# SeptinaryAI_Balldi__elec_power__power_20.net
KiCad netlist of a schematic drawn in Altium Designer
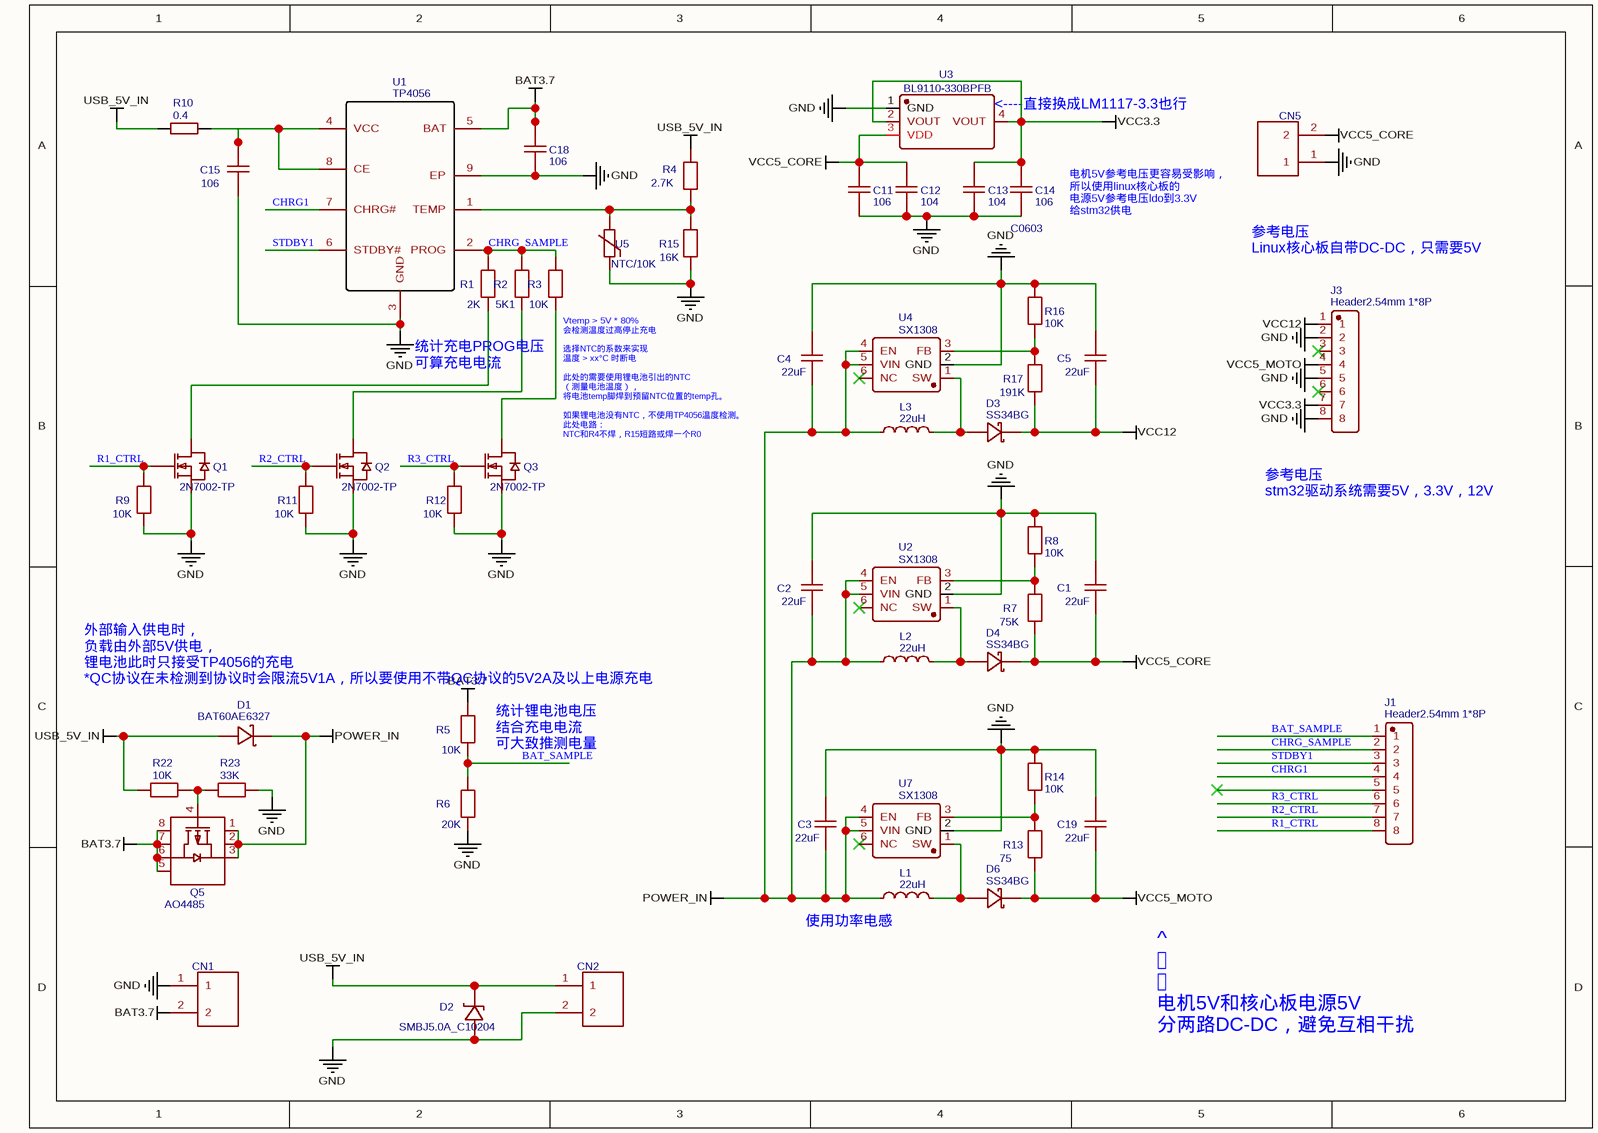
[diagram p0: SeptinaryAI_Balldi__elec_power__power_2023-07-21.schdoc]

(export (version "E")
  (design (tool "Eeschema 10.0.6"))
  (components
    (comp (ref "C1")
      (value "22uF")
      (fields (field (name "CONTRIBUTOR") "LCSC"))
      (libsource (lib "altium-import") (part "root_1_22uF_"))
    )
    (comp (ref "C2")
      (value "22uF")
      (fields (field (name "CONTRIBUTOR") "LCSC"))
      (libsource (lib "altium-import") (part "root_1_22uF_"))
    )
    (comp (ref "C3")
      (value "22uF")
      (fields (field (name "CONTRIBUTOR") "LCSC"))
      (libsource (lib "altium-import") (part "root_1_22uF_"))
    )
    (comp (ref "C4")
      (value "22uF")
      (fields (field (name "CONTRIBUTOR") "LCSC"))
      (libsource (lib "altium-import") (part "root_1_22uF_"))
    )
    (comp (ref "C5")
      (value "22uF")
      (fields (field (name "CONTRIBUTOR") "LCSC"))
      (libsource (lib "altium-import") (part "root_1_22uF_"))
    )
    (comp (ref "C11")
      (value "106")
      (fields
        (field (name "BOM_SUPPLIER PART") "C2762283")
        (field (name "BOM_MANUFACTURER PART") "CL10F104ZO8NNNC")
        (field (name "CONTRIBUTOR") "LCSC")
      )
      (libsource (lib "altium-import") (part "root_1_106_"))
    )
    (comp (ref "C12")
      (value "104")
      (fields
        (field (name "BOM_SUPPLIER PART") "C2762283")
        (field (name "BOM_MANUFACTURER PART") "CL10F104ZO8NNNC")
        (field (name "CONTRIBUTOR") "LCSC")
      )
      (libsource (lib "altium-import") (part "root_1_104_"))
    )
    (comp (ref "C13")
      (value "104")
      (fields
        (field (name "BOM_SUPPLIER PART") "C2762283")
        (field (name "BOM_MANUFACTURER PART") "CL10F104ZO8NNNC")
        (field (name "CONTRIBUTOR") "LCSC")
      )
      (libsource (lib "altium-import") (part "root_1_104_"))
    )
    (comp (ref "C14")
      (value "106")
      (fields
        (field (name "BOM_SUPPLIER PART") "C2762283")
        (field (name "BOM_MANUFACTURER PART") "CL10F104ZO8NNNC")
        (field (name "CONTRIBUTOR") "LCSC")
      )
      (libsource (lib "altium-import") (part "root_1_106_"))
    )
    (comp (ref "C15")
      (value "106")
      (fields (field (name "CONTRIBUTOR") "LCSC"))
      (libsource (lib "altium-import") (part "root_1_106_"))
    )
    (comp (ref "C18")
      (value "106")
      (fields (field (name "CONTRIBUTOR") "LCSC"))
      (libsource (lib "altium-import") (part "root_1_106_"))
    )
    (comp (ref "C19")
      (value "22uF")
      (fields (field (name "CONTRIBUTOR") "LCSC"))
      (libsource (lib "altium-import") (part "root_1_22uF_"))
    )
    (comp (ref "CN1") (value "640454-2") (libsource (lib "altium-import") (part "root_0_640454-2_")))
    (comp (ref "CN2") (value "640454-2") (libsource (lib "altium-import") (part "root_0_640454-2_")))
    (comp (ref "CN5") (value "640454-2") (libsource (lib "altium-import") (part "root_2_640454-2_")))
    (comp (ref "D1")
      (value "BAT60AE6327")
      (fields (field (name "CONTRIBUTOR") "LCSC"))
      (libsource (lib "altium-import") (part "root_0_BAT60AE6327_"))
    )
    (comp (ref "D2")
      (value "SMBJ5.0A_C10204")
      (libsource (lib "altium-import") (part "root_3_SMBJ5.0A_C10204_"))
    )
    (comp (ref "D3")
      (value "SS34BG")
      (fields (field (name "BOM_SUPPLIER PART") "C719397") (field (name "CONTRIBUTOR") "LCSC"))
      (libsource (lib "altium-import") (part "root_2_SS34BG_"))
    )
    (comp (ref "D4")
      (value "SS34BG")
      (fields (field (name "BOM_SUPPLIER PART") "C719397") (field (name "CONTRIBUTOR") "LCSC"))
      (libsource (lib "altium-import") (part "root_2_SS34BG_"))
    )
    (comp (ref "D6")
      (value "SS34BG")
      (fields (field (name "BOM_SUPPLIER PART") "C719397") (field (name "CONTRIBUTOR") "LCSC"))
      (libsource (lib "altium-import") (part "root_2_SS34BG_"))
    )
    (comp (ref "J1")
      (value "Header2.54mm 1*8P")
      (libsource (lib "altium-import") (part "root_0_Header2.54mm 1*8P_"))
    )
    (comp (ref "J3")
      (value "Header2.54mm 1*8P")
      (libsource (lib "altium-import") (part "root_0_Header2.54mm 1*8P_"))
    )
    (comp (ref "L1")
      (value "22uH")
      (fields
        (field (name "BOM_MANUFACTURER PART") "SPM10040T-220M")
        (field (name "BOM_SUPPLIER PART") "C138686")
      )
      (libsource (lib "altium-import") (part "root_0_22uH_"))
    )
    (comp (ref "L2")
      (value "22uH")
      (fields
        (field (name "BOM_MANUFACTURER PART") "SPM10040T-220M")
        (field (name "BOM_SUPPLIER PART") "C138686")
      )
      (libsource (lib "altium-import") (part "root_0_22uH_"))
    )
    (comp (ref "L3")
      (value "22uH")
      (fields
        (field (name "BOM_MANUFACTURER PART") "SPM10040T-220M")
        (field (name "BOM_SUPPLIER PART") "C138686")
      )
      (libsource (lib "altium-import") (part "root_0_22uH_"))
    )
    (comp (ref "Q1")
      (value "2N7002-TP")
      (fields (field (name "CONTRIBUTOR") "LCSC"))
      (libsource (lib "altium-import") (part "root_0_2N7002-TP_"))
    )
    (comp (ref "Q2")
      (value "2N7002-TP")
      (fields (field (name "CONTRIBUTOR") "LCSC"))
      (libsource (lib "altium-import") (part "root_0_2N7002-TP_"))
    )
    (comp (ref "Q3")
      (value "2N7002-TP")
      (fields (field (name "CONTRIBUTOR") "LCSC"))
      (libsource (lib "altium-import") (part "root_0_2N7002-TP_"))
    )
    (comp (ref "Q5")
      (value "AO4485")
      (fields (field (name "BOM_SUPPLIER PART") "C51499"))
      (libsource (lib "altium-import") (part "root_3_AO4485_"))
    )
    (comp (ref "R1")
      (value "2K")
      (fields (field (name "CONTRIBUTOR") "LCSC"))
      (libsource (lib "altium-import") (part "root_3_2K_"))
    )
    (comp (ref "R2")
      (value "5K1")
      (fields (field (name "CONTRIBUTOR") "LCSC"))
      (libsource (lib "altium-import") (part "root_3_5K1_"))
    )
    (comp (ref "R3")
      (value "10K")
      (fields (field (name "CONTRIBUTOR") "LCSC"))
      (libsource (lib "altium-import") (part "root_3_10K_"))
    )
    (comp (ref "R4")
      (value "2.7K")
      (fields (field (name "CONTRIBUTOR") "LCSC"))
      (libsource (lib "altium-import") (part "root_3_2.7K_"))
    )
    (comp (ref "R5")
      (value "10K")
      (fields (field (name "CONTRIBUTOR") "LCSC"))
      (libsource (lib "altium-import") (part "root_3_10K_"))
    )
    (comp (ref "R6")
      (value "20K")
      (fields (field (name "CONTRIBUTOR") "LCSC"))
      (libsource (lib "altium-import") (part "root_3_20K_"))
    )
    (comp (ref "R7")
      (value "75K")
      (fields (field (name "CONTRIBUTOR") "LCSC"))
      (libsource (lib "altium-import") (part "root_3_75K_"))
    )
    (comp (ref "R8")
      (value "10K")
      (fields (field (name "CONTRIBUTOR") "LCSC"))
      (libsource (lib "altium-import") (part "root_1_10K_"))
    )
    (comp (ref "R9")
      (value "10K")
      (fields (field (name "CONTRIBUTOR") "LCSC"))
      (libsource (lib "altium-import") (part "root_3_10K_"))
    )
    (comp (ref "R10") (value "0.4") (libsource (lib "altium-import") (part "root_0_0.4_")))
    (comp (ref "R11")
      (value "10K")
      (fields (field (name "CONTRIBUTOR") "LCSC"))
      (libsource (lib "altium-import") (part "root_3_10K_"))
    )
    (comp (ref "R12")
      (value "10K")
      (fields (field (name "CONTRIBUTOR") "LCSC"))
      (libsource (lib "altium-import") (part "root_3_10K_"))
    )
    (comp (ref "R13")
      (value "75")
      (fields (field (name "CONTRIBUTOR") "LCSC"))
      (libsource (lib "altium-import") (part "root_3_75_"))
    )
    (comp (ref "R14")
      (value "10K")
      (fields (field (name "CONTRIBUTOR") "LCSC"))
      (libsource (lib "altium-import") (part "root_1_10K_"))
    )
    (comp (ref "R15")
      (value "16K")
      (fields (field (name "CONTRIBUTOR") "LCSC"))
      (libsource (lib "altium-import") (part "root_3_16K_"))
    )
    (comp (ref "R16")
      (value "10K")
      (fields (field (name "CONTRIBUTOR") "LCSC"))
      (libsource (lib "altium-import") (part "root_1_10K_"))
    )
    (comp (ref "R17")
      (value "191K")
      (fields (field (name "CONTRIBUTOR") "LCSC"))
      (libsource (lib "altium-import") (part "root_3_191K_"))
    )
    (comp (ref "R22")
      (value "10K")
      (fields (field (name "CONTRIBUTOR") "LCSC"))
      (libsource (lib "altium-import") (part "root_0_10K_"))
    )
    (comp (ref "R23")
      (value "33K")
      (fields (field (name "CONTRIBUTOR") "LCSC"))
      (libsource (lib "altium-import") (part "root_0_33K_"))
    )
    (comp (ref "U1")
      (value "TP4056")
      (fields (field (name "CONTRIBUTOR") "Guest"))
      (libsource (lib "altium-import") (part "root_0_TP4056_"))
    )
    (comp (ref "U2") (value "SX1308") (libsource (lib "altium-import") (part "root_2_SX1308_")))
    (comp (ref "U3")
      (value "BL9110-330BPFB")
      (fields (field (name "BOM_SUPPLIER PART") "C169246") (field (name "CONTRIBUTOR") "LCSC"))
      (libsource (lib "altium-import") (part "root_0_BL9110-330BPFB_"))
    )
    (comp (ref "U4") (value "SX1308") (libsource (lib "altium-import") (part "root_2_SX1308_")))
    (comp (ref "U5")
      (value "NTC/10K")
      (fields (field (name "BOM_SUPPLIER PART") "C9900004021") (field (name "CONTRIBUTOR") "LCSC"))
      (libsource (lib "altium-import") (part "root_1_NTC/10K_"))
    )
    (comp (ref "U7") (value "SX1308") (libsource (lib "altium-import") (part "root_2_SX1308_")))
  )
  (nets
    (net (code "1") (name "/BAT_SAMPLE") (class "Default")
      (node (ref "J1") (pin "1") (pinfunction "1_1") (pintype "passive"))
      (node (ref "R5") (pin "2") (pinfunction "2_2") (pintype "passive"))
      (node (ref "R6") (pin "1") (pinfunction "1_1") (pintype "passive"))
    )
    (net (code "2") (name "/CHRG1") (class "Default")
      (node (ref "J1") (pin "4") (pinfunction "4_4") (pintype "passive"))
      (node (ref "U1") (pin "7") (pinfunction "CHRG#_7") (pintype "passive"))
    )
    (net (code "3") (name "/CHRG_SAMPLE") (class "Default")
      (node (ref "J1") (pin "2") (pinfunction "2_2") (pintype "passive"))
      (node (ref "R1") (pin "1") (pinfunction "1_1") (pintype "passive"))
      (node (ref "R2") (pin "1") (pinfunction "1_1") (pintype "passive"))
      (node (ref "R3") (pin "1") (pinfunction "1_1") (pintype "passive"))
      (node (ref "U1") (pin "2") (pinfunction "PROG_2") (pintype "passive"))
    )
    (net (code "4") (name "/R1_CTRL") (class "Default")
      (node (ref "J1") (pin "8") (pinfunction "8_8") (pintype "passive"))
      (node (ref "Q1") (pin "1") (pinfunction "G_1") (pintype "passive"))
      (node (ref "R9") (pin "1") (pinfunction "1_1") (pintype "passive"))
    )
    (net (code "5") (name "/R2_CTRL") (class "Default")
      (node (ref "J1") (pin "7") (pinfunction "7_7") (pintype "passive"))
      (node (ref "Q2") (pin "1") (pinfunction "G_1") (pintype "passive"))
      (node (ref "R11") (pin "1") (pinfunction "1_1") (pintype "passive"))
    )
    (net (code "6") (name "/R3_CTRL") (class "Default")
      (node (ref "J1") (pin "6") (pinfunction "6_6") (pintype "passive"))
      (node (ref "Q3") (pin "1") (pinfunction "G_1") (pintype "passive"))
      (node (ref "R12") (pin "1") (pinfunction "1_1") (pintype "passive"))
    )
    (net (code "7") (name "/STDBY1") (class "Default")
      (node (ref "J1") (pin "3") (pinfunction "3_3") (pintype "passive"))
      (node (ref "U1") (pin "6") (pinfunction "STDBY#_6") (pintype "passive"))
    )
    (net (code "8") (name "BAT3.7") (class "Default")
      (node (ref "C18") (pin "2") (pinfunction "2_2") (pintype "passive"))
      (node (ref "CN1") (pin "2") (pinfunction "2_2") (pintype "passive"))
      (node (ref "Q5") (pin "5") (pinfunction "D_5") (pintype "passive"))
      (node (ref "Q5") (pin "6") (pinfunction "D_6") (pintype "passive"))
      (node (ref "Q5") (pin "7") (pinfunction "D_7") (pintype "passive"))
      (node (ref "Q5") (pin "8") (pinfunction "D_8") (pintype "passive"))
      (node (ref "R5") (pin "1") (pinfunction "1_1") (pintype "passive"))
      (node (ref "U1") (pin "5") (pinfunction "BAT_5") (pintype "passive"))
    )
    (net (code "9") (name "GND") (class "Default")
      (node (ref "C1") (pin "2") (pinfunction "2_2") (pintype "passive"))
      (node (ref "C11") (pin "1") (pinfunction "1_1") (pintype "passive"))
      (node (ref "C12") (pin "1") (pinfunction "1_1") (pintype "passive"))
      (node (ref "C13") (pin "1") (pinfunction "1_1") (pintype "passive"))
      (node (ref "C14") (pin "1") (pinfunction "1_1") (pintype "passive"))
      (node (ref "C15") (pin "1") (pinfunction "1_1") (pintype "passive"))
      (node (ref "C18") (pin "1") (pinfunction "1_1") (pintype "passive"))
      (node (ref "C19") (pin "2") (pinfunction "2_2") (pintype "passive"))
      (node (ref "C2") (pin "2") (pinfunction "2_2") (pintype "passive"))
      (node (ref "C3") (pin "2") (pinfunction "2_2") (pintype "passive"))
      (node (ref "C4") (pin "2") (pinfunction "2_2") (pintype "passive"))
      (node (ref "C5") (pin "2") (pinfunction "2_2") (pintype "passive"))
      (node (ref "CN1") (pin "1") (pinfunction "1_1") (pintype "passive"))
      (node (ref "CN2") (pin "2") (pinfunction "2_2") (pintype "passive"))
      (node (ref "CN5") (pin "1") (pinfunction "1_1") (pintype "passive"))
      (node (ref "D2") (pin "1") (pinfunction "A_1") (pintype "passive"))
      (node (ref "J3") (pin "2") (pinfunction "2_2") (pintype "passive"))
      (node (ref "J3") (pin "5") (pinfunction "5_5") (pintype "passive"))
      (node (ref "J3") (pin "8") (pinfunction "8_8") (pintype "passive"))
      (node (ref "Q1") (pin "2") (pinfunction "S_2") (pintype "passive"))
      (node (ref "Q2") (pin "2") (pinfunction "S_2") (pintype "passive"))
      (node (ref "Q3") (pin "2") (pinfunction "S_2") (pintype "passive"))
      (node (ref "R11") (pin "2") (pinfunction "2_2") (pintype "passive"))
      (node (ref "R12") (pin "2") (pinfunction "2_2") (pintype "passive"))
      (node (ref "R14") (pin "2") (pinfunction "2_2") (pintype "passive"))
      (node (ref "R15") (pin "2") (pinfunction "2_2") (pintype "passive"))
      (node (ref "R16") (pin "2") (pinfunction "2_2") (pintype "passive"))
      (node (ref "R23") (pin "2") (pinfunction "2_2") (pintype "passive"))
      (node (ref "R6") (pin "2") (pinfunction "2_2") (pintype "passive"))
      (node (ref "R8") (pin "2") (pinfunction "2_2") (pintype "passive"))
      (node (ref "R9") (pin "2") (pinfunction "2_2") (pintype "passive"))
      (node (ref "U1") (pin "3") (pinfunction "GND_3") (pintype "passive"))
      (node (ref "U1") (pin "9") (pinfunction "EP_9") (pintype "passive"))
      (node (ref "U2") (pin "2") (pinfunction "GND_2") (pintype "passive"))
      (node (ref "U3") (pin "1") (pinfunction "GND_1") (pintype "passive"))
      (node (ref "U4") (pin "2") (pinfunction "GND_2") (pintype "passive"))
      (node (ref "U5") (pin "1") (pinfunction "1_1") (pintype "passive"))
      (node (ref "U7") (pin "2") (pinfunction "GND_2") (pintype "passive"))
    )
    (net (code "10") (name "Net-(D3-A)") (class "Default")
      (node (ref "D3") (pin "2") (pinfunction "A_2") (pintype "passive"))
      (node (ref "L3") (pin "2") (pinfunction "2_2") (pintype "passive"))
      (node (ref "U4") (pin "1") (pinfunction "SW_1") (pintype "passive"))
    )
    (net (code "11") (name "Net-(D4-A)") (class "Default")
      (node (ref "D4") (pin "2") (pinfunction "A_2") (pintype "passive"))
      (node (ref "L2") (pin "2") (pinfunction "2_2") (pintype "passive"))
      (node (ref "U2") (pin "1") (pinfunction "SW_1") (pintype "passive"))
    )
    (net (code "12") (name "Net-(D6-A)") (class "Default")
      (node (ref "D6") (pin "2") (pinfunction "A_2") (pintype "passive"))
      (node (ref "L1") (pin "2") (pinfunction "2_2") (pintype "passive"))
      (node (ref "U7") (pin "1") (pinfunction "SW_1") (pintype "passive"))
    )
    (net (code "13") (name "Net-(Q1-D)") (class "Default")
      (node (ref "Q1") (pin "3") (pinfunction "D_3") (pintype "passive"))
      (node (ref "R1") (pin "2") (pinfunction "2_2") (pintype "passive"))
    )
    (net (code "14") (name "Net-(Q2-D)") (class "Default")
      (node (ref "Q2") (pin "3") (pinfunction "D_3") (pintype "passive"))
      (node (ref "R2") (pin "2") (pinfunction "2_2") (pintype "passive"))
    )
    (net (code "15") (name "Net-(Q3-D)") (class "Default")
      (node (ref "Q3") (pin "3") (pinfunction "D_3") (pintype "passive"))
      (node (ref "R3") (pin "2") (pinfunction "2_2") (pintype "passive"))
    )
    (net (code "16") (name "Net-(Q5-G)") (class "Default")
      (node (ref "Q5") (pin "4") (pinfunction "G_4") (pintype "passive"))
      (node (ref "R22") (pin "2") (pinfunction "2_2") (pintype "passive"))
      (node (ref "R23") (pin "1") (pinfunction "1_1") (pintype "passive"))
    )
    (net (code "17") (name "Net-(U1-CE)") (class "Default")
      (node (ref "C15") (pin "2") (pinfunction "2_2") (pintype "passive"))
      (node (ref "R10") (pin "2") (pinfunction "2_2") (pintype "passive"))
      (node (ref "U1") (pin "4") (pinfunction "VCC_4") (pintype "passive"))
      (node (ref "U1") (pin "8") (pinfunction "CE_8") (pintype "passive"))
    )
    (net (code "18") (name "Net-(U1-TEMP)") (class "Default")
      (node (ref "R15") (pin "1") (pinfunction "1_1") (pintype "passive"))
      (node (ref "R4") (pin "2") (pinfunction "2_2") (pintype "passive"))
      (node (ref "U1") (pin "1") (pinfunction "TEMP_1") (pintype "passive"))
      (node (ref "U5") (pin "2") (pinfunction "2_2") (pintype "passive"))
    )
    (net (code "19") (name "Net-(U2-FB)") (class "Default")
      (node (ref "R7") (pin "1") (pinfunction "1_1") (pintype "passive"))
      (node (ref "R8") (pin "1") (pinfunction "1_1") (pintype "passive"))
      (node (ref "U2") (pin "3") (pinfunction "FB_3") (pintype "passive"))
    )
    (net (code "20") (name "Net-(U4-FB)") (class "Default")
      (node (ref "R16") (pin "1") (pinfunction "1_1") (pintype "passive"))
      (node (ref "R17") (pin "1") (pinfunction "1_1") (pintype "passive"))
      (node (ref "U4") (pin "3") (pinfunction "FB_3") (pintype "passive"))
    )
    (net (code "21") (name "Net-(U7-FB)") (class "Default")
      (node (ref "R13") (pin "1") (pinfunction "1_1") (pintype "passive"))
      (node (ref "R14") (pin "1") (pinfunction "1_1") (pintype "passive"))
      (node (ref "U7") (pin "3") (pinfunction "FB_3") (pintype "passive"))
    )
    (net (code "22") (name "POWER_IN") (class "Default")
      (node (ref "C2") (pin "1") (pinfunction "1_1") (pintype "passive"))
      (node (ref "C3") (pin "1") (pinfunction "1_1") (pintype "passive"))
      (node (ref "C4") (pin "1") (pinfunction "1_1") (pintype "passive"))
      (node (ref "D1") (pin "2") (pinfunction "K_2") (pintype "passive"))
      (node (ref "L1") (pin "1") (pinfunction "1_1") (pintype "passive"))
      (node (ref "L2") (pin "1") (pinfunction "1_1") (pintype "passive"))
      (node (ref "L3") (pin "1") (pinfunction "1_1") (pintype "passive"))
      (node (ref "Q5") (pin "1") (pinfunction "S_1") (pintype "passive"))
      (node (ref "Q5") (pin "2") (pinfunction "S_2") (pintype "passive"))
      (node (ref "Q5") (pin "3") (pinfunction "S_3") (pintype "passive"))
      (node (ref "U2") (pin "4") (pinfunction "EN_4") (pintype "passive"))
      (node (ref "U2") (pin "5") (pinfunction "VIN_5") (pintype "passive"))
      (node (ref "U4") (pin "4") (pinfunction "EN_4") (pintype "passive"))
      (node (ref "U4") (pin "5") (pinfunction "VIN_5") (pintype "passive"))
      (node (ref "U7") (pin "4") (pinfunction "EN_4") (pintype "passive"))
      (node (ref "U7") (pin "5") (pinfunction "VIN_5") (pintype "passive"))
    )
    (net (code "23") (name "USB_5V_IN") (class "Default")
      (node (ref "CN2") (pin "1") (pinfunction "1_1") (pintype "passive"))
      (node (ref "D1") (pin "1") (pinfunction "A_1") (pintype "passive"))
      (node (ref "D2") (pin "2") (pinfunction "K_2") (pintype "passive"))
      (node (ref "R10") (pin "1") (pinfunction "1_1") (pintype "passive"))
      (node (ref "R22") (pin "1") (pinfunction "1_1") (pintype "passive"))
      (node (ref "R4") (pin "1") (pinfunction "1_1") (pintype "passive"))
    )
    (net (code "24") (name "VCC3.3") (class "Default")
      (node (ref "C13") (pin "2") (pinfunction "2_2") (pintype "passive"))
      (node (ref "C14") (pin "2") (pinfunction "2_2") (pintype "passive"))
      (node (ref "J3") (pin "7") (pinfunction "7_7") (pintype "passive"))
      (node (ref "U3") (pin "2") (pinfunction "VOUT_2") (pintype "passive"))
      (node (ref "U3") (pin "4") (pinfunction "VOUT_4") (pintype "passive"))
    )
    (net (code "25") (name "VCC5_CORE") (class "Default")
      (node (ref "C1") (pin "1") (pinfunction "1_1") (pintype "passive"))
      (node (ref "C11") (pin "2") (pinfunction "2_2") (pintype "passive"))
      (node (ref "C12") (pin "2") (pinfunction "2_2") (pintype "passive"))
      (node (ref "CN5") (pin "2") (pinfunction "2_2") (pintype "passive"))
      (node (ref "D4") (pin "1") (pinfunction "K_1") (pintype "passive"))
      (node (ref "R7") (pin "2") (pinfunction "2_2") (pintype "passive"))
      (node (ref "U3") (pin "3") (pinfunction "VDD_3") (pintype "passive"))
    )
    (net (code "26") (name "VCC5_MOTO") (class "Default")
      (node (ref "C19") (pin "1") (pinfunction "1_1") (pintype "passive"))
      (node (ref "D6") (pin "1") (pinfunction "K_1") (pintype "passive"))
      (node (ref "J3") (pin "4") (pinfunction "4_4") (pintype "passive"))
      (node (ref "R13") (pin "2") (pinfunction "2_2") (pintype "passive"))
    )
    (net (code "27") (name "VCC12") (class "Default")
      (node (ref "C5") (pin "1") (pinfunction "1_1") (pintype "passive"))
      (node (ref "D3") (pin "1") (pinfunction "K_1") (pintype "passive"))
      (node (ref "J3") (pin "1") (pinfunction "1_1") (pintype "passive"))
      (node (ref "R17") (pin "2") (pinfunction "2_2") (pintype "passive"))
    )
    (net (code "28") (name "unconnected-(J1-Pad5)") (class "Default")
      (node (ref "J1") (pin "5") (pinfunction "5_5") (pintype "passive+no_connect"))
    )
    (net (code "29") (name "unconnected-(J3-Pad3)") (class "Default")
      (node (ref "J3") (pin "3") (pinfunction "3_3") (pintype "passive+no_connect"))
    )
    (net (code "30") (name "unconnected-(J3-Pad6)") (class "Default")
      (node (ref "J3") (pin "6") (pinfunction "6_6") (pintype "passive+no_connect"))
    )
    (net (code "31") (name "unconnected-(U2-NC-Pad6)") (class "Default")
      (node (ref "U2") (pin "6") (pinfunction "NC_6") (pintype "passive+no_connect"))
    )
    (net (code "32") (name "unconnected-(U4-NC-Pad6)") (class "Default")
      (node (ref "U4") (pin "6") (pinfunction "NC_6") (pintype "passive+no_connect"))
    )
    (net (code "33") (name "unconnected-(U7-NC-Pad6)") (class "Default")
      (node (ref "U7") (pin "6") (pinfunction "NC_6") (pintype "passive+no_connect"))
    )
  )
)
